# micromouse2018_v1.net
KiCad netlist of a schematic drawn in EAGLE
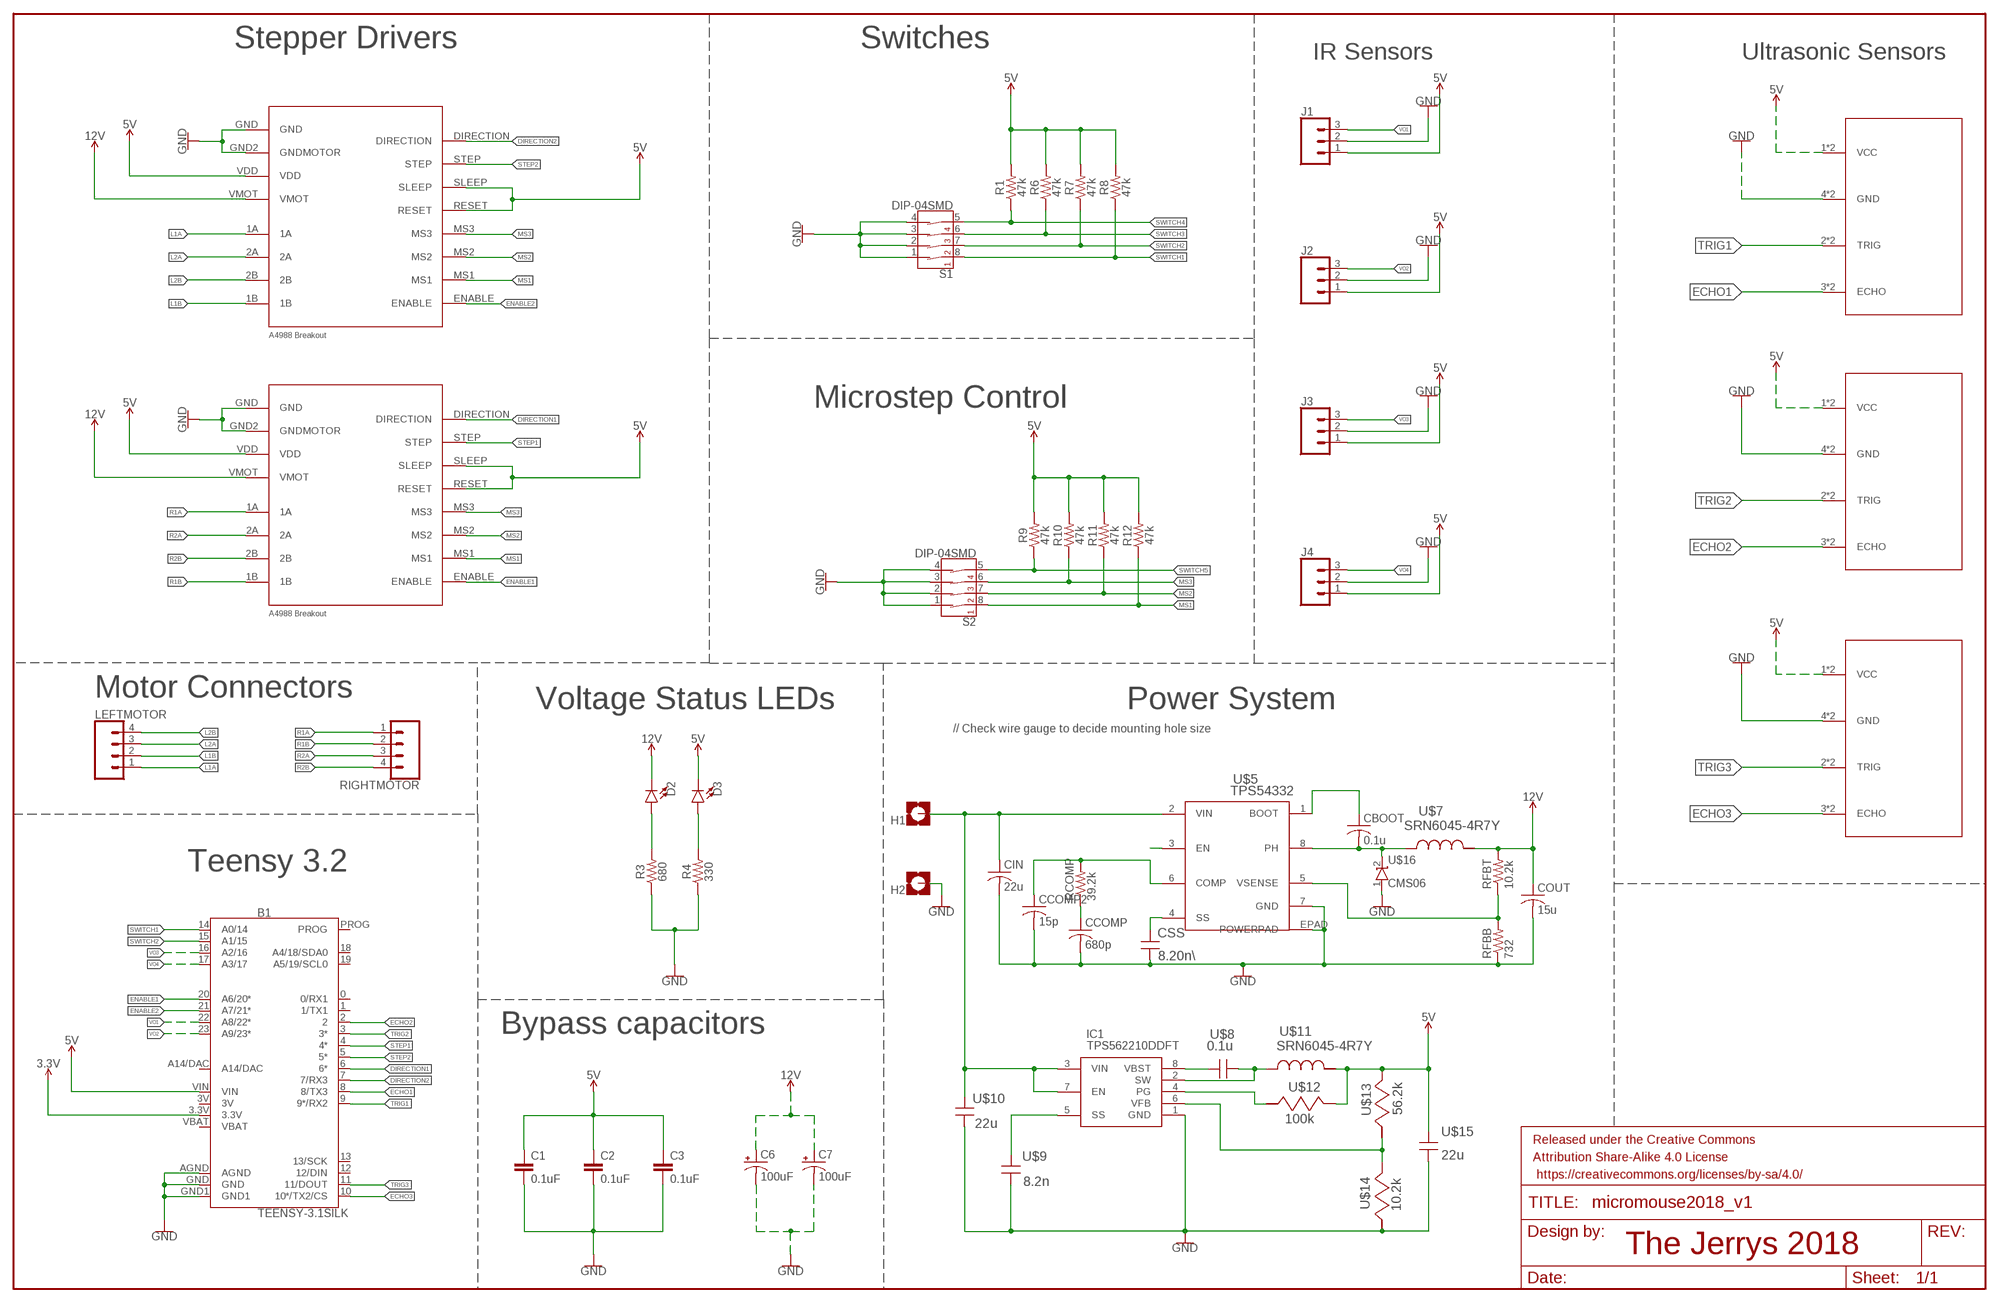
[diagram p0: schematic, sheet 1]

(export (version "E")
  (design (tool "Eeschema 10.0.6"))
  (components
    (comp (ref "B1")
      (value "TEENSY-3.1SILK")
      (footprint "eagle-import:TEENSY-3.1")
      (libsource (lib "eagle-import") (part "TEENSY-3.1SILK"))
    )
    (comp (ref "C1")
      (value "0.1uF")
      (footprint "eagle-import:0603")
      (libsource (lib "eagle-import") (part "0.1UF-0603-25V-(+80/-20%)"))
    )
    (comp (ref "C2")
      (value "0.1uF")
      (footprint "eagle-import:0603")
      (libsource (lib "eagle-import") (part "0.1UF-0603-25V-(+80/-20%)"))
    )
    (comp (ref "C3")
      (value "0.1uF")
      (footprint "eagle-import:0603")
      (libsource (lib "eagle-import") (part "0.1UF-0603-25V-(+80/-20%)"))
    )
    (comp (ref "C6")
      (value "100uF")
      (footprint "eagle-import:PANASONIC_D")
      (libsource (lib "eagle-import") (part "100UF-POLAR-25V-20%(ELEC)"))
    )
    (comp (ref "C7")
      (value "100uF")
      (footprint "eagle-import:PANASONIC_D")
      (libsource (lib "eagle-import") (part "100UF-POLAR-25V-20%(ELEC)"))
    )
    (comp (ref "CBOOT")
      (value "0.1u")
      (footprint "eagle-import:C0805")
      (libsource (lib "eagle-import") (part "resistor_348_C-USC0805"))
    )
    (comp (ref "CCOMP")
      (value "680p")
      (footprint "eagle-import:C0805")
      (libsource (lib "eagle-import") (part "resistor_348_C-USC0805"))
    )
    (comp (ref "CCOMP2")
      (value "15p")
      (footprint "eagle-import:C0805")
      (libsource (lib "eagle-import") (part "resistor_348_C-USC0805"))
    )
    (comp (ref "CIN")
      (value "22u")
      (footprint "eagle-import:C1210")
      (libsource (lib "eagle-import") (part "C-USC1210"))
    )
    (comp (ref "COUT")
      (value "15u")
      (footprint "eagle-import:C0805")
      (libsource (lib "eagle-import") (part "resistor_348_C-USC0805"))
    )
    (comp (ref "CSS")
      (value "8.20n\\")
      (footprint "eagle-import:1206")
      (fields (field (name "MANUFACTURER_PART_NUMBER") "12063A822JAT2A"))
      (libsource (lib "eagle-import") (part "12063A822JAT2A"))
    )
    (comp (ref "D2")
      (value "LED0603")
      (footprint "eagle-import:LED-0603")
      (libsource (lib "eagle-import") (part "LED0603"))
    )
    (comp (ref "D3")
      (value "LED0603")
      (footprint "eagle-import:LED-0603")
      (libsource (lib "eagle-import") (part "LED0603"))
    )
    (comp (ref "FRAME1")
      (value "FRAME-LEDGER")
      (footprint "eagle-import:CREATIVE_COMMONS")
      (libsource (lib "eagle-import") (part "FRAME-LEDGER"))
    )
    (comp (ref "H1")
      (value "MOUNT-PAD-SQUARE2.8")
      (footprint "eagle-import:2,8-PAD-SQUARE")
      (libsource (lib "eagle-import") (part "MOUNT-PAD-SQUARE2.8"))
    )
    (comp (ref "H2")
      (value "MOUNT-PAD-SQUARE2.8")
      (footprint "eagle-import:2,8-PAD-SQUARE")
      (libsource (lib "eagle-import") (part "MOUNT-PAD-SQUARE2.8"))
    )
    (comp (ref "IC1")
      (value "TPS562210DDFT")
      (footprint "eagle-import:SOT65P280X110-8N")
      (fields (field (name "RS_PART_NUMBER") "9009845"))
      (libsource (lib "eagle-import") (part "TPS562210DDFT"))
    )
    (comp (ref "J1")
      (value "CONN_03JST-PTH-VERT")
      (footprint "eagle-import:JST-3-PTH-VERT")
      (libsource (lib "eagle-import") (part "CONN_03JST-PTH-VERT"))
    )
    (comp (ref "J2")
      (value "CONN_03JST-PTH-VERT")
      (footprint "eagle-import:JST-3-PTH-VERT")
      (libsource (lib "eagle-import") (part "CONN_03JST-PTH-VERT"))
    )
    (comp (ref "J3")
      (value "CONN_03JST-PTH-VERT")
      (footprint "eagle-import:JST-3-PTH-VERT")
      (libsource (lib "eagle-import") (part "CONN_03JST-PTH-VERT"))
    )
    (comp (ref "J4")
      (value "CONN_03JST-PTH-VERT")
      (footprint "eagle-import:JST-3-PTH-VERT")
      (libsource (lib "eagle-import") (part "CONN_03JST-PTH-VERT"))
    )
    (comp (ref "LEFTMOTOR")
      (value "CONN_04LONGPADS")
      (footprint "eagle-import:1X04_LONGPADS")
      (libsource (lib "eagle-import") (part "CONN_04LONGPADS"))
    )
    (comp (ref "R1")
      (value "47k")
      (footprint "eagle-import:0603")
      (libsource (lib "eagle-import") (part "47KOHM-0603-1/10W-1%"))
    )
    (comp (ref "R3")
      (value "680")
      (footprint "eagle-import:0603")
      (libsource (lib "eagle-import") (part "680OHM-0603-1/10W-5%"))
    )
    (comp (ref "R4")
      (value "330")
      (footprint "eagle-import:0603")
      (libsource (lib "eagle-import") (part "330OHM-0603-1/10W-1%"))
    )
    (comp (ref "R6")
      (value "47k")
      (footprint "eagle-import:0603")
      (libsource (lib "eagle-import") (part "47KOHM-0603-1/10W-1%"))
    )
    (comp (ref "R7")
      (value "47k")
      (footprint "eagle-import:0603")
      (libsource (lib "eagle-import") (part "47KOHM-0603-1/10W-1%"))
    )
    (comp (ref "R8")
      (value "47k")
      (footprint "eagle-import:0603")
      (libsource (lib "eagle-import") (part "47KOHM-0603-1/10W-1%"))
    )
    (comp (ref "R9")
      (value "47k")
      (footprint "eagle-import:0603")
      (libsource (lib "eagle-import") (part "47KOHM-0603-1/10W-1%"))
    )
    (comp (ref "R10")
      (value "47k")
      (footprint "eagle-import:0603")
      (libsource (lib "eagle-import") (part "47KOHM-0603-1/10W-1%"))
    )
    (comp (ref "R11")
      (value "47k")
      (footprint "eagle-import:0603")
      (libsource (lib "eagle-import") (part "47KOHM-0603-1/10W-1%"))
    )
    (comp (ref "R12")
      (value "47k")
      (footprint "eagle-import:0603")
      (libsource (lib "eagle-import") (part "47KOHM-0603-1/10W-1%"))
    )
    (comp (ref "RCOMP")
      (value "39.2k")
      (footprint "eagle-import:R0805")
      (libsource (lib "eagle-import") (part "R-US_R0805"))
    )
    (comp (ref "RFBB")
      (value "732")
      (footprint "eagle-import:R0805")
      (libsource (lib "eagle-import") (part "R-US_R0805"))
    )
    (comp (ref "RFBT")
      (value "10.2k")
      (footprint "eagle-import:R0805")
      (libsource (lib "eagle-import") (part "R-US_R0805"))
    )
    (comp (ref "RIGHTMOTOR")
      (value "CONN_04LONGPADS")
      (footprint "eagle-import:1X04_LONGPADS")
      (libsource (lib "eagle-import") (part "CONN_04LONGPADS"))
    )
    (comp (ref "S1")
      (value "DIP-04SMD")
      (footprint "eagle-import:DIPSWITCH-04-SMD")
      (libsource (lib "eagle-import") (part "DIP-04SMD"))
    )
    (comp (ref "S2")
      (value "DIP-04SMD")
      (footprint "eagle-import:DIPSWITCH-04-SMD")
      (libsource (lib "eagle-import") (part "DIP-04SMD"))
    )
    (comp (ref "U$1")
      (value "A4988_BREAKOUT")
      (footprint "eagle-import:A4988_BREAKOUT")
      (libsource (lib "eagle-import") (part "A4988_BREAKOUT"))
    )
    (comp (ref "U$2")
      (value "A4988_BREAKOUT")
      (footprint "eagle-import:A4988_BREAKOUT")
      (libsource (lib "eagle-import") (part "A4988_BREAKOUT"))
    )
    (comp (ref "U$3")
      (value "ULTRASONIC")
      (footprint "eagle-import:1X04_SMD_VERTICAL_COMBO")
      (libsource (lib "eagle-import") (part "ULTRASONIC"))
    )
    (comp (ref "U$4")
      (value "ULTRASONIC")
      (footprint "eagle-import:1X04_SMD_VERTICAL_COMBO")
      (libsource (lib "eagle-import") (part "ULTRASONIC"))
    )
    (comp (ref "U$5")
      (value "TPS54332")
      (footprint "eagle-import:DDA8_2P13X3-M")
      (libsource (lib "eagle-import") (part "TPS54332"))
    )
    (comp (ref "U$6")
      (value "ULTRASONIC")
      (footprint "eagle-import:1X04_SMD_VERTICAL_COMBO")
      (libsource (lib "eagle-import") (part "ULTRASONIC"))
    )
    (comp (ref "U$7")
      (value "SRN6045-4R7Y")
      (footprint "eagle-import:SRN6045")
      (fields (field (name "MANUFACTURER_PART_NUMBER") "SRN60454R7Y"))
      (libsource (lib "eagle-import") (part "SRN6045-4R7Y"))
    )
    (comp (ref "U$8")
      (value "0.1u")
      (footprint "eagle-import:0805")
      (fields (field (name "MANUFACTURER_PART_NUMBER") "08053C104KAT2A"))
      (libsource (lib "eagle-import") (part "08053C104KAT2A"))
    )
    (comp (ref "U$9")
      (value "8.2n")
      (footprint "eagle-import:1206")
      (fields (field (name "MANUFACTURER_PART_NUMBER") "12063A822JAT2A"))
      (libsource (lib "eagle-import") (part "12063A822JAT2A"))
    )
    (comp (ref "U$10")
      (value "22u")
      (footprint "eagle-import:1210")
      (fields (field (name "MANUFACTURER_PART_NUMBER") "GRM32ER61E226KE15L"))
      (libsource (lib "eagle-import") (part "GRM32ER61E226KE15L"))
    )
    (comp (ref "U$11")
      (value "SRN6045-4R7Y")
      (footprint "eagle-import:SRN6045")
      (fields (field (name "MANUFACTURER_PART_NUMBER") "SRN60454R7Y"))
      (libsource (lib "eagle-import") (part "SRN6045-4R7Y"))
    )
    (comp (ref "U$12")
      (value "100k")
      (footprint "eagle-import:0805")
      (fields
        (field (name "MANUFACTURER_PART_NUMBER") "RR1220P104D")
        (field (name "POWER") "0.1")
        (field (name "TOLERANCE") "0.5")
      )
      (libsource (lib "eagle-import") (part "RR1220P-104-D"))
    )
    (comp (ref "U$13")
      (value "56.2k")
      (footprint "eagle-import:0805")
      (fields
        (field (name "MANUFACTURER_PART_NUMBER") "ERJ6ENF5622V")
        (field (name "POWER") "0.125")
        (field (name "TOLERANCE") "1.0")
      )
      (libsource (lib "eagle-import") (part "ERJ-6ENF5622V"))
    )
    (comp (ref "U$14")
      (value "10.2k")
      (footprint "eagle-import:0805")
      (fields
        (field (name "MANUFACTURER_PART_NUMBER") "ERJ6ENF1022V")
        (field (name "POWER") "0.125")
        (field (name "TOLERANCE") "1.0")
      )
      (libsource (lib "eagle-import") (part "ERJ-6ENF1022V"))
    )
    (comp (ref "U$15")
      (value "22u")
      (footprint "eagle-import:1206_190")
      (fields (field (name "MANUFACTURER_PART_NUMBER") "GRM31CR61A226KE19L"))
      (libsource (lib "eagle-import") (part "GRM31CR61A226KE19L"))
    )
    (comp (ref "U$16")
      (value "CMS06")
      (footprint "eagle-import:SODFL4724X108N")
      (libsource (lib "eagle-import") (part "CMS06"))
    )
  )
  (nets
    (net (code "1") (name "/3V") (class "Default")
      (node (ref "B1") (pin "3V") (pinfunction "3V_3V") (pintype "power_in"))
    )
    (net (code "2") (name "/VBAT") (class "Default")
      (node (ref "B1") (pin "VBAT") (pinfunction "VBAT_VBAT") (pintype "power_in"))
    )
    (net (code "3") (name "3.3V") (class "Default")
      (node (ref "B1") (pin "3.3V") (pinfunction "3.3V_3.3V") (pintype "power_in"))
    )
    (net (code "4") (name "5V") (class "Default")
      (node (ref "B1") (pin "VIN") (pinfunction "VIN_VIN") (pintype "power_in"))
      (node (ref "C1") (pin "1") (pinfunction "1_1") (pintype "passive"))
      (node (ref "C2") (pin "1") (pinfunction "1_1") (pintype "passive"))
      (node (ref "C3") (pin "1") (pinfunction "1_1") (pintype "passive"))
      (node (ref "D3") (pin "C") (pinfunction "C_C") (pintype "passive"))
      (node (ref "J1") (pin "1") (pinfunction "1_1") (pintype "passive"))
      (node (ref "J2") (pin "1") (pinfunction "1_1") (pintype "passive"))
      (node (ref "J3") (pin "1") (pinfunction "1_1") (pintype "passive"))
      (node (ref "J4") (pin "1") (pinfunction "1_1") (pintype "passive"))
      (node (ref "R1") (pin "2") (pinfunction "2_2") (pintype "passive"))
      (node (ref "R10") (pin "2") (pinfunction "2_2") (pintype "passive"))
      (node (ref "R11") (pin "2") (pinfunction "2_2") (pintype "passive"))
      (node (ref "R12") (pin "2") (pinfunction "2_2") (pintype "passive"))
      (node (ref "R6") (pin "2") (pinfunction "2_2") (pintype "passive"))
      (node (ref "R7") (pin "2") (pinfunction "2_2") (pintype "passive"))
      (node (ref "R8") (pin "2") (pinfunction "2_2") (pintype "passive"))
      (node (ref "R9") (pin "2") (pinfunction "2_2") (pintype "passive"))
      (node (ref "U$1") (pin "RESET") (pinfunction "RESET_RESET") (pintype "bidirectional"))
      (node (ref "U$1") (pin "SLEEP") (pinfunction "SLEEP_SLEEP") (pintype "bidirectional"))
      (node (ref "U$1") (pin "VDD") (pinfunction "VDD_VDD") (pintype "bidirectional"))
      (node (ref "U$11") (pin "2") (pinfunction "2_2") (pintype "passive"))
      (node (ref "U$12") (pin "1") (pinfunction "1_1") (pintype "passive"))
      (node (ref "U$13") (pin "1") (pinfunction "1_1") (pintype "passive"))
      (node (ref "U$15") (pin "1") (pinfunction "1_1") (pintype "passive"))
      (node (ref "U$2") (pin "RESET") (pinfunction "RESET_RESET") (pintype "bidirectional"))
      (node (ref "U$2") (pin "SLEEP") (pinfunction "SLEEP_SLEEP") (pintype "bidirectional"))
      (node (ref "U$2") (pin "VDD") (pinfunction "VDD_VDD") (pintype "bidirectional"))
      (node (ref "U$3") (pin "1") (pinfunction "VCC_1") (pintype "bidirectional"))
      (node (ref "U$3") (pin "1-2") (pinfunction "VCC_1-2") (pintype "bidirectional"))
      (node (ref "U$4") (pin "1") (pinfunction "VCC_1") (pintype "bidirectional"))
      (node (ref "U$4") (pin "1-2") (pinfunction "VCC_1-2") (pintype "bidirectional"))
      (node (ref "U$6") (pin "1") (pinfunction "VCC_1") (pintype "bidirectional"))
      (node (ref "U$6") (pin "1-2") (pinfunction "VCC_1-2") (pintype "bidirectional"))
    )
    (net (code "5") (name "12V") (class "Default")
      (node (ref "C6") (pin "+") (pinfunction "+_+") (pintype "passive"))
      (node (ref "C7") (pin "+") (pinfunction "+_+") (pintype "passive"))
      (node (ref "COUT") (pin "1") (pinfunction "1_1") (pintype "passive"))
      (node (ref "D2") (pin "C") (pinfunction "C_C") (pintype "passive"))
      (node (ref "RFBT") (pin "2") (pinfunction "2_2") (pintype "passive"))
      (node (ref "U$1") (pin "VMOT") (pinfunction "VMOT_VMOT") (pintype "bidirectional"))
      (node (ref "U$2") (pin "VMOT") (pinfunction "VMOT_VMOT") (pintype "bidirectional"))
      (node (ref "U$7") (pin "2") (pinfunction "2_2") (pintype "passive"))
    )
    (net (code "6") (name "DIRECTION1") (class "Default")
      (node (ref "B1") (pin "6") (pinfunction "6*_6") (pintype "bidirectional"))
      (node (ref "U$2") (pin "DIRECTION") (pinfunction "DIRECTION_DIRECTION") (pintype "bidirectional"))
    )
    (net (code "7") (name "DIRECTION2") (class "Default")
      (node (ref "B1") (pin "7") (pinfunction "7/RX3_7") (pintype "bidirectional"))
      (node (ref "U$1") (pin "DIRECTION") (pinfunction "DIRECTION_DIRECTION") (pintype "bidirectional"))
    )
    (net (code "8") (name "ECHO1") (class "Default")
      (node (ref "B1") (pin "8") (pinfunction "8/TX3_8") (pintype "bidirectional"))
      (node (ref "U$3") (pin "3") (pinfunction "ECHO_3") (pintype "bidirectional"))
      (node (ref "U$3") (pin "3-2") (pinfunction "ECHO_3-2") (pintype "bidirectional"))
    )
    (net (code "9") (name "ECHO2") (class "Default")
      (node (ref "B1") (pin "2") (pinfunction "2_2") (pintype "bidirectional"))
      (node (ref "U$4") (pin "3") (pinfunction "ECHO_3") (pintype "bidirectional"))
      (node (ref "U$4") (pin "3-2") (pinfunction "ECHO_3-2") (pintype "bidirectional"))
    )
    (net (code "10") (name "ECHO3") (class "Default")
      (node (ref "B1") (pin "10") (pinfunction "10*/TX2/CS_10") (pintype "bidirectional"))
      (node (ref "U$6") (pin "3") (pinfunction "ECHO_3") (pintype "bidirectional"))
      (node (ref "U$6") (pin "3-2") (pinfunction "ECHO_3-2") (pintype "bidirectional"))
    )
    (net (code "11") (name "ENABLE1") (class "Default")
      (node (ref "B1") (pin "20") (pinfunction "A6/20*_20") (pintype "bidirectional"))
      (node (ref "U$2") (pin "ENABLE") (pinfunction "ENABLE_ENABLE") (pintype "bidirectional"))
    )
    (net (code "12") (name "ENABLE2") (class "Default")
      (node (ref "B1") (pin "21") (pinfunction "A7/21*_21") (pintype "bidirectional"))
      (node (ref "U$1") (pin "ENABLE") (pinfunction "ENABLE_ENABLE") (pintype "bidirectional"))
    )
    (net (code "13") (name "GND") (class "Default")
      (node (ref "B1") (pin "AGND") (pinfunction "AGND_AGND") (pintype "power_in"))
      (node (ref "B1") (pin "GND") (pinfunction "GND_GND") (pintype "power_in"))
      (node (ref "B1") (pin "GND1") (pinfunction "GND1_GND1") (pintype "power_in"))
      (node (ref "C1") (pin "2") (pinfunction "2_2") (pintype "passive"))
      (node (ref "C2") (pin "2") (pinfunction "2_2") (pintype "passive"))
      (node (ref "C3") (pin "2") (pinfunction "2_2") (pintype "passive"))
      (node (ref "C6") (pin "-") (pinfunction "-_-") (pintype "passive"))
      (node (ref "C7") (pin "-") (pinfunction "-_-") (pintype "passive"))
      (node (ref "CCOMP") (pin "2") (pinfunction "2_2") (pintype "passive"))
      (node (ref "CCOMP2") (pin "2") (pinfunction "2_2") (pintype "passive"))
      (node (ref "CIN") (pin "2") (pinfunction "2_2") (pintype "passive"))
      (node (ref "COUT") (pin "2") (pinfunction "2_2") (pintype "passive"))
      (node (ref "CSS") (pin "1") (pinfunction "1_1") (pintype "passive"))
      (node (ref "H2") (pin "B2,8") (pinfunction "MOUNT_B2,8") (pintype "passive"))
      (node (ref "IC1") (pin "1") (pinfunction "GND_1") (pintype "input"))
      (node (ref "J1") (pin "2") (pinfunction "2_2") (pintype "passive"))
      (node (ref "J2") (pin "2") (pinfunction "2_2") (pintype "passive"))
      (node (ref "J3") (pin "2") (pinfunction "2_2") (pintype "passive"))
      (node (ref "J4") (pin "2") (pinfunction "2_2") (pintype "passive"))
      (node (ref "R3") (pin "1") (pinfunction "1_1") (pintype "passive"))
      (node (ref "R4") (pin "1") (pinfunction "1_1") (pintype "passive"))
      (node (ref "RFBB") (pin "1") (pinfunction "1_1") (pintype "passive"))
      (node (ref "S1") (pin "1") (pinfunction "1A_1") (pintype "bidirectional"))
      (node (ref "S1") (pin "2") (pinfunction "2A_2") (pintype "bidirectional"))
      (node (ref "S1") (pin "3") (pinfunction "3A_3") (pintype "bidirectional"))
      (node (ref "S1") (pin "4") (pinfunction "4A_4") (pintype "bidirectional"))
      (node (ref "S2") (pin "1") (pinfunction "1A_1") (pintype "bidirectional"))
      (node (ref "S2") (pin "2") (pinfunction "2A_2") (pintype "bidirectional"))
      (node (ref "S2") (pin "3") (pinfunction "3A_3") (pintype "bidirectional"))
      (node (ref "S2") (pin "4") (pinfunction "4A_4") (pintype "bidirectional"))
      (node (ref "U$1") (pin "GND") (pinfunction "GND_GND") (pintype "bidirectional"))
      (node (ref "U$1") (pin "GND2") (pinfunction "GNDMOTOR_GND2") (pintype "bidirectional"))
      (node (ref "U$10") (pin "2") (pinfunction "2_2") (pintype "passive"))
      (node (ref "U$14") (pin "2") (pinfunction "2_2") (pintype "passive"))
      (node (ref "U$15") (pin "2") (pinfunction "2_2") (pintype "passive"))
      (node (ref "U$16") (pin "1") (pinfunction "A_1") (pintype "input"))
      (node (ref "U$2") (pin "GND") (pinfunction "GND_GND") (pintype "bidirectional"))
      (node (ref "U$2") (pin "GND2") (pinfunction "GNDMOTOR_GND2") (pintype "bidirectional"))
      (node (ref "U$3") (pin "4") (pinfunction "GND_4") (pintype "bidirectional"))
      (node (ref "U$3") (pin "4-2") (pinfunction "GND_4-2") (pintype "bidirectional"))
      (node (ref "U$4") (pin "4") (pinfunction "GND_4") (pintype "bidirectional"))
      (node (ref "U$4") (pin "4-2") (pinfunction "GND_4-2") (pintype "bidirectional"))
      (node (ref "U$5") (pin "7") (pinfunction "GND_7") (pintype "bidirectional"))
      (node (ref "U$5") (pin "EPAD") (pinfunction "POWERPAD_EPAD") (pintype "bidirectional"))
      (node (ref "U$6") (pin "4") (pinfunction "GND_4") (pintype "bidirectional"))
      (node (ref "U$6") (pin "4-2") (pinfunction "GND_4-2") (pintype "bidirectional"))
      (node (ref "U$9") (pin "2") (pinfunction "2_2") (pintype "passive"))
    )
    (net (code "14") (name "L1A") (class "Default")
      (node (ref "LEFTMOTOR") (pin "1") (pinfunction "1_1") (pintype "passive"))
      (node (ref "U$1") (pin "1A") (pinfunction "1A_1A") (pintype "bidirectional"))
    )
    (net (code "15") (name "L1B") (class "Default")
      (node (ref "LEFTMOTOR") (pin "2") (pinfunction "2_2") (pintype "passive"))
      (node (ref "U$1") (pin "1B") (pinfunction "1B_1B") (pintype "bidirectional"))
    )
    (net (code "16") (name "L2A") (class "Default")
      (node (ref "LEFTMOTOR") (pin "3") (pinfunction "3_3") (pintype "passive"))
      (node (ref "U$1") (pin "2A") (pinfunction "2A_2A") (pintype "bidirectional"))
    )
    (net (code "17") (name "L2B") (class "Default")
      (node (ref "LEFTMOTOR") (pin "4") (pinfunction "4_4") (pintype "passive"))
      (node (ref "U$1") (pin "2B") (pinfunction "2B_2B") (pintype "bidirectional"))
    )
    (net (code "18") (name "MS1") (class "Default")
      (node (ref "R12") (pin "1") (pinfunction "1_1") (pintype "passive"))
      (node (ref "S2") (pin "8") (pinfunction "1B_8") (pintype "bidirectional"))
      (node (ref "U$1") (pin "MS1") (pinfunction "MS1_MS1") (pintype "bidirectional"))
      (node (ref "U$2") (pin "MS1") (pinfunction "MS1_MS1") (pintype "bidirectional"))
    )
    (net (code "19") (name "MS2") (class "Default")
      (node (ref "R11") (pin "1") (pinfunction "1_1") (pintype "passive"))
      (node (ref "S2") (pin "7") (pinfunction "2B_7") (pintype "bidirectional"))
      (node (ref "U$1") (pin "MS2") (pinfunction "MS2_MS2") (pintype "bidirectional"))
      (node (ref "U$2") (pin "MS2") (pinfunction "MS2_MS2") (pintype "bidirectional"))
    )
    (net (code "20") (name "MS3") (class "Default")
      (node (ref "R10") (pin "1") (pinfunction "1_1") (pintype "passive"))
      (node (ref "S2") (pin "6") (pinfunction "3B_6") (pintype "bidirectional"))
      (node (ref "U$1") (pin "MS3") (pinfunction "MS3_MS3") (pintype "bidirectional"))
      (node (ref "U$2") (pin "MS3") (pinfunction "MS3_MS3") (pintype "bidirectional"))
    )
    (net (code "21") (name "Net-(CCOMP-Pad1)") (class "Default")
      (node (ref "CCOMP") (pin "1") (pinfunction "1_1") (pintype "passive"))
      (node (ref "RCOMP") (pin "1") (pinfunction "1_1") (pintype "passive"))
    )
    (net (code "22") (name "Net-(D2-PadA)") (class "Default")
      (node (ref "D2") (pin "A") (pinfunction "A_A") (pintype "passive"))
      (node (ref "R3") (pin "2") (pinfunction "2_2") (pintype "passive"))
    )
    (net (code "23") (name "Net-(D3-PadA)") (class "Default")
      (node (ref "D3") (pin "A") (pinfunction "A_A") (pintype "passive"))
      (node (ref "R4") (pin "2") (pinfunction "2_2") (pintype "passive"))
    )
    (net (code "24") (name "Net-(H1-MOUNT)") (class "Default")
      (node (ref "CIN") (pin "1") (pinfunction "1_1") (pintype "passive"))
      (node (ref "H1") (pin "B2,8") (pinfunction "MOUNT_B2,8") (pintype "passive"))
      (node (ref "IC1") (pin "3") (pinfunction "VIN_3") (pintype "input"))
      (node (ref "IC1") (pin "7") (pinfunction "EN_7") (pintype "input"))
      (node (ref "U$10") (pin "1") (pinfunction "1_1") (pintype "passive"))
      (node (ref "U$5") (pin "2") (pinfunction "VIN_2") (pintype "bidirectional"))
    )
    (net (code "25") (name "Net-(IC1-PG)") (class "Default")
      (node (ref "IC1") (pin "4") (pinfunction "PG_4") (pintype "input"))
      (node (ref "U$12") (pin "2") (pinfunction "2_2") (pintype "passive"))
    )
    (net (code "26") (name "Net-(IC1-SS)") (class "Default")
      (node (ref "IC1") (pin "5") (pinfunction "SS_5") (pintype "input"))
      (node (ref "U$9") (pin "1") (pinfunction "1_1") (pintype "passive"))
    )
    (net (code "27") (name "Net-(IC1-SW)") (class "Default")
      (node (ref "IC1") (pin "2") (pinfunction "SW_2") (pintype "input"))
      (node (ref "U$11") (pin "1") (pinfunction "1_1") (pintype "passive"))
      (node (ref "U$8") (pin "1") (pinfunction "1_1") (pintype "passive"))
    )
    (net (code "28") (name "Net-(IC1-VBST)") (class "Default")
      (node (ref "IC1") (pin "8") (pinfunction "VBST_8") (pintype "input"))
      (node (ref "U$8") (pin "2") (pinfunction "2_2") (pintype "passive"))
    )
    (net (code "29") (name "Net-(IC1-VFB)") (class "Default")
      (node (ref "IC1") (pin "6") (pinfunction "VFB_6") (pintype "input"))
      (node (ref "U$13") (pin "2") (pinfunction "2_2") (pintype "passive"))
      (node (ref "U$14") (pin "1") (pinfunction "1_1") (pintype "passive"))
    )
    (net (code "30") (name "Net-(U$5-BOOT)") (class "Default")
      (node (ref "CBOOT") (pin "1") (pinfunction "1_1") (pintype "passive"))
      (node (ref "U$5") (pin "1") (pinfunction "BOOT_1") (pintype "bidirectional"))
    )
    (net (code "31") (name "Net-(U$5-COMP)") (class "Default")
      (node (ref "CCOMP2") (pin "1") (pinfunction "1_1") (pintype "passive"))
      (node (ref "RCOMP") (pin "2") (pinfunction "2_2") (pintype "passive"))
      (node (ref "U$5") (pin "6") (pinfunction "COMP_6") (pintype "bidirectional"))
    )
    (net (code "32") (name "Net-(U$5-SS)") (class "Default")
      (node (ref "CSS") (pin "2") (pinfunction "2_2") (pintype "passive"))
      (node (ref "U$5") (pin "4") (pinfunction "SS_4") (pintype "bidirectional"))
    )
    (net (code "33") (name "Net-(U$5-VSENSE)") (class "Default")
      (node (ref "RFBB") (pin "2") (pinfunction "2_2") (pintype "passive"))
      (node (ref "RFBT") (pin "1") (pinfunction "1_1") (pintype "passive"))
      (node (ref "U$5") (pin "5") (pinfunction "VSENSE_5") (pintype "bidirectional"))
    )
    (net (code "34") (name "Net-(U$16-K)") (class "Default")
      (node (ref "CBOOT") (pin "2") (pinfunction "2_2") (pintype "passive"))
      (node (ref "U$16") (pin "2") (pinfunction "K_2") (pintype "input"))
      (node (ref "U$5") (pin "8") (pinfunction "PH_8") (pintype "bidirectional"))
      (node (ref "U$7") (pin "1") (pinfunction "1_1") (pintype "passive"))
    )
    (net (code "35") (name "R1A") (class "Default")
      (node (ref "RIGHTMOTOR") (pin "1") (pinfunction "1_1") (pintype "passive"))
      (node (ref "U$2") (pin "1A") (pinfunction "1A_1A") (pintype "bidirectional"))
    )
    (net (code "36") (name "R1B") (class "Default")
      (node (ref "RIGHTMOTOR") (pin "2") (pinfunction "2_2") (pintype "passive"))
      (node (ref "U$2") (pin "1B") (pinfunction "1B_1B") (pintype "bidirectional"))
    )
    (net (code "37") (name "R2A") (class "Default")
      (node (ref "RIGHTMOTOR") (pin "3") (pinfunction "3_3") (pintype "passive"))
      (node (ref "U$2") (pin "2A") (pinfunction "2A_2A") (pintype "bidirectional"))
    )
    (net (code "38") (name "R2B") (class "Default")
      (node (ref "RIGHTMOTOR") (pin "4") (pinfunction "4_4") (pintype "passive"))
      (node (ref "U$2") (pin "2B") (pinfunction "2B_2B") (pintype "bidirectional"))
    )
    (net (code "39") (name "STEP1") (class "Default")
      (node (ref "B1") (pin "4") (pinfunction "4*_4") (pintype "bidirectional"))
      (node (ref "U$2") (pin "STEP") (pinfunction "STEP_STEP") (pintype "bidirectional"))
    )
    (net (code "40") (name "STEP2") (class "Default")
      (node (ref "B1") (pin "5") (pinfunction "5*_5") (pintype "bidirectional"))
      (node (ref "U$1") (pin "STEP") (pinfunction "STEP_STEP") (pintype "bidirectional"))
    )
    (net (code "41") (name "SWITCH1") (class "Default")
      (node (ref "B1") (pin "14") (pinfunction "A0/14_14") (pintype "bidirectional"))
      (node (ref "R8") (pin "1") (pinfunction "1_1") (pintype "passive"))
      (node (ref "S1") (pin "8") (pinfunction "1B_8") (pintype "bidirectional"))
    )
    (net (code "42") (name "SWITCH2") (class "Default")
      (node (ref "B1") (pin "15") (pinfunction "A1/15_15") (pintype "bidirectional"))
      (node (ref "R7") (pin "1") (pinfunction "1_1") (pintype "passive"))
      (node (ref "S1") (pin "7") (pinfunction "2B_7") (pintype "bidirectional"))
    )
    (net (code "43") (name "SWITCH3") (class "Default")
      (node (ref "R6") (pin "1") (pinfunction "1_1") (pintype "passive"))
      (node (ref "S1") (pin "6") (pinfunction "3B_6") (pintype "bidirectional"))
    )
    (net (code "44") (name "SWITCH4") (class "Default")
      (node (ref "R1") (pin "1") (pinfunction "1_1") (pintype "passive"))
      (node (ref "S1") (pin "5") (pinfunction "4B_5") (pintype "bidirectional"))
    )
    (net (code "45") (name "SWITCH5") (class "Default")
      (node (ref "R9") (pin "1") (pinfunction "1_1") (pintype "passive"))
      (node (ref "S2") (pin "5") (pinfunction "4B_5") (pintype "bidirectional"))
    )
    (net (code "46") (name "TRIG1") (class "Default")
      (node (ref "B1") (pin "9") (pinfunction "9*/RX2_9") (pintype "bidirectional"))
      (node (ref "U$3") (pin "2") (pinfunction "TRIG_2") (pintype "bidirectional"))
      (node (ref "U$3") (pin "2-2") (pinfunction "TRIG_2-2") (pintype "bidirectional"))
    )
    (net (code "47") (name "TRIG2") (class "Default")
      (node (ref "B1") (pin "3") (pinfunction "3*_3") (pintype "bidirectional"))
      (node (ref "U$4") (pin "2") (pinfunction "TRIG_2") (pintype "bidirectional"))
      (node (ref "U$4") (pin "2-2") (pinfunction "TRIG_2-2") (pintype "bidirectional"))
    )
    (net (code "48") (name "TRIG3") (class "Default")
      (node (ref "B1") (pin "11") (pinfunction "11/DOUT_11") (pintype "bidirectional"))
      (node (ref "U$6") (pin "2") (pinfunction "TRIG_2") (pintype "bidirectional"))
      (node (ref "U$6") (pin "2-2") (pinfunction "TRIG_2-2") (pintype "bidirectional"))
    )
    (net (code "49") (name "VO1") (class "Default")
      (node (ref "B1") (pin "22") (pinfunction "A8/22*_22") (pintype "bidirectional"))
      (node (ref "J1") (pin "3") (pinfunction "3_3") (pintype "passive"))
    )
    (net (code "50") (name "VO2") (class "Default")
      (node (ref "B1") (pin "23") (pinfunction "A9/23*_23") (pintype "bidirectional"))
      (node (ref "J2") (pin "3") (pinfunction "3_3") (pintype "passive"))
    )
    (net (code "51") (name "VO3") (class "Default")
      (node (ref "B1") (pin "16") (pinfunction "A2/16_16") (pintype "bidirectional"))
      (node (ref "J3") (pin "3") (pinfunction "3_3") (pintype "passive"))
    )
    (net (code "52") (name "VO4") (class "Default")
      (node (ref "B1") (pin "17") (pinfunction "A3/17_17") (pintype "bidirectional"))
      (node (ref "J4") (pin "3") (pinfunction "3_3") (pintype "passive"))
    )
    (net (code "53") (name "unconnected-(B1-0{slash}RX1-Pad0)") (class "Default")
      (node (ref "B1") (pin "0") (pinfunction "0/RX1_0") (pintype "bidirectional"))
    )
    (net (code "54") (name "unconnected-(B1-1{slash}TX1-Pad1)") (class "Default")
      (node (ref "B1") (pin "1") (pinfunction "1/TX1_1") (pintype "bidirectional"))
    )
    (net (code "55") (name "unconnected-(B1-12{slash}DIN-Pad12)") (class "Default")
      (node (ref "B1") (pin "12") (pinfunction "12/DIN_12") (pintype "bidirectional"))
    )
    (net (code "56") (name "unconnected-(B1-13{slash}SCK-Pad13)") (class "Default")
      (node (ref "B1") (pin "13") (pinfunction "13/SCK_13") (pintype "bidirectional"))
    )
    (net (code "57") (name "unconnected-(B1-A4{slash}18{slash}SDA0-Pad18)") (class "Default")
      (node (ref "B1") (pin "18") (pinfunction "A4/18/SDA0_18") (pintype "bidirectional"))
    )
    (net (code "58") (name "unconnected-(B1-A5{slash}19{slash}SCL0-Pad19)") (class "Default")
      (node (ref "B1") (pin "19") (pinfunction "A5/19/SCL0_19") (pintype "bidirectional"))
    )
    (net (code "59") (name "unconnected-(B1-PadA14{slash}DAC)") (class "Default")
      (node (ref "B1") (pin "A14/DAC") (pinfunction "A14/DAC_A14/DAC") (pintype "bidirectional"))
    )
    (net (code "60") (name "unconnected-(B1-PadPROG)") (class "Default")
      (node (ref "B1") (pin "PROG") (pinfunction "PROG_PROG") (pintype "bidirectional"))
    )
    (net (code "61") (name "unconnected-(U$5-EN-Pad3)") (class "Default")
      (node (ref "U$5") (pin "3") (pinfunction "EN_3") (pintype "bidirectional"))
    )
  )
)
